# EnviroTron.net
KiCad netlist of a schematic drawn in EAGLE
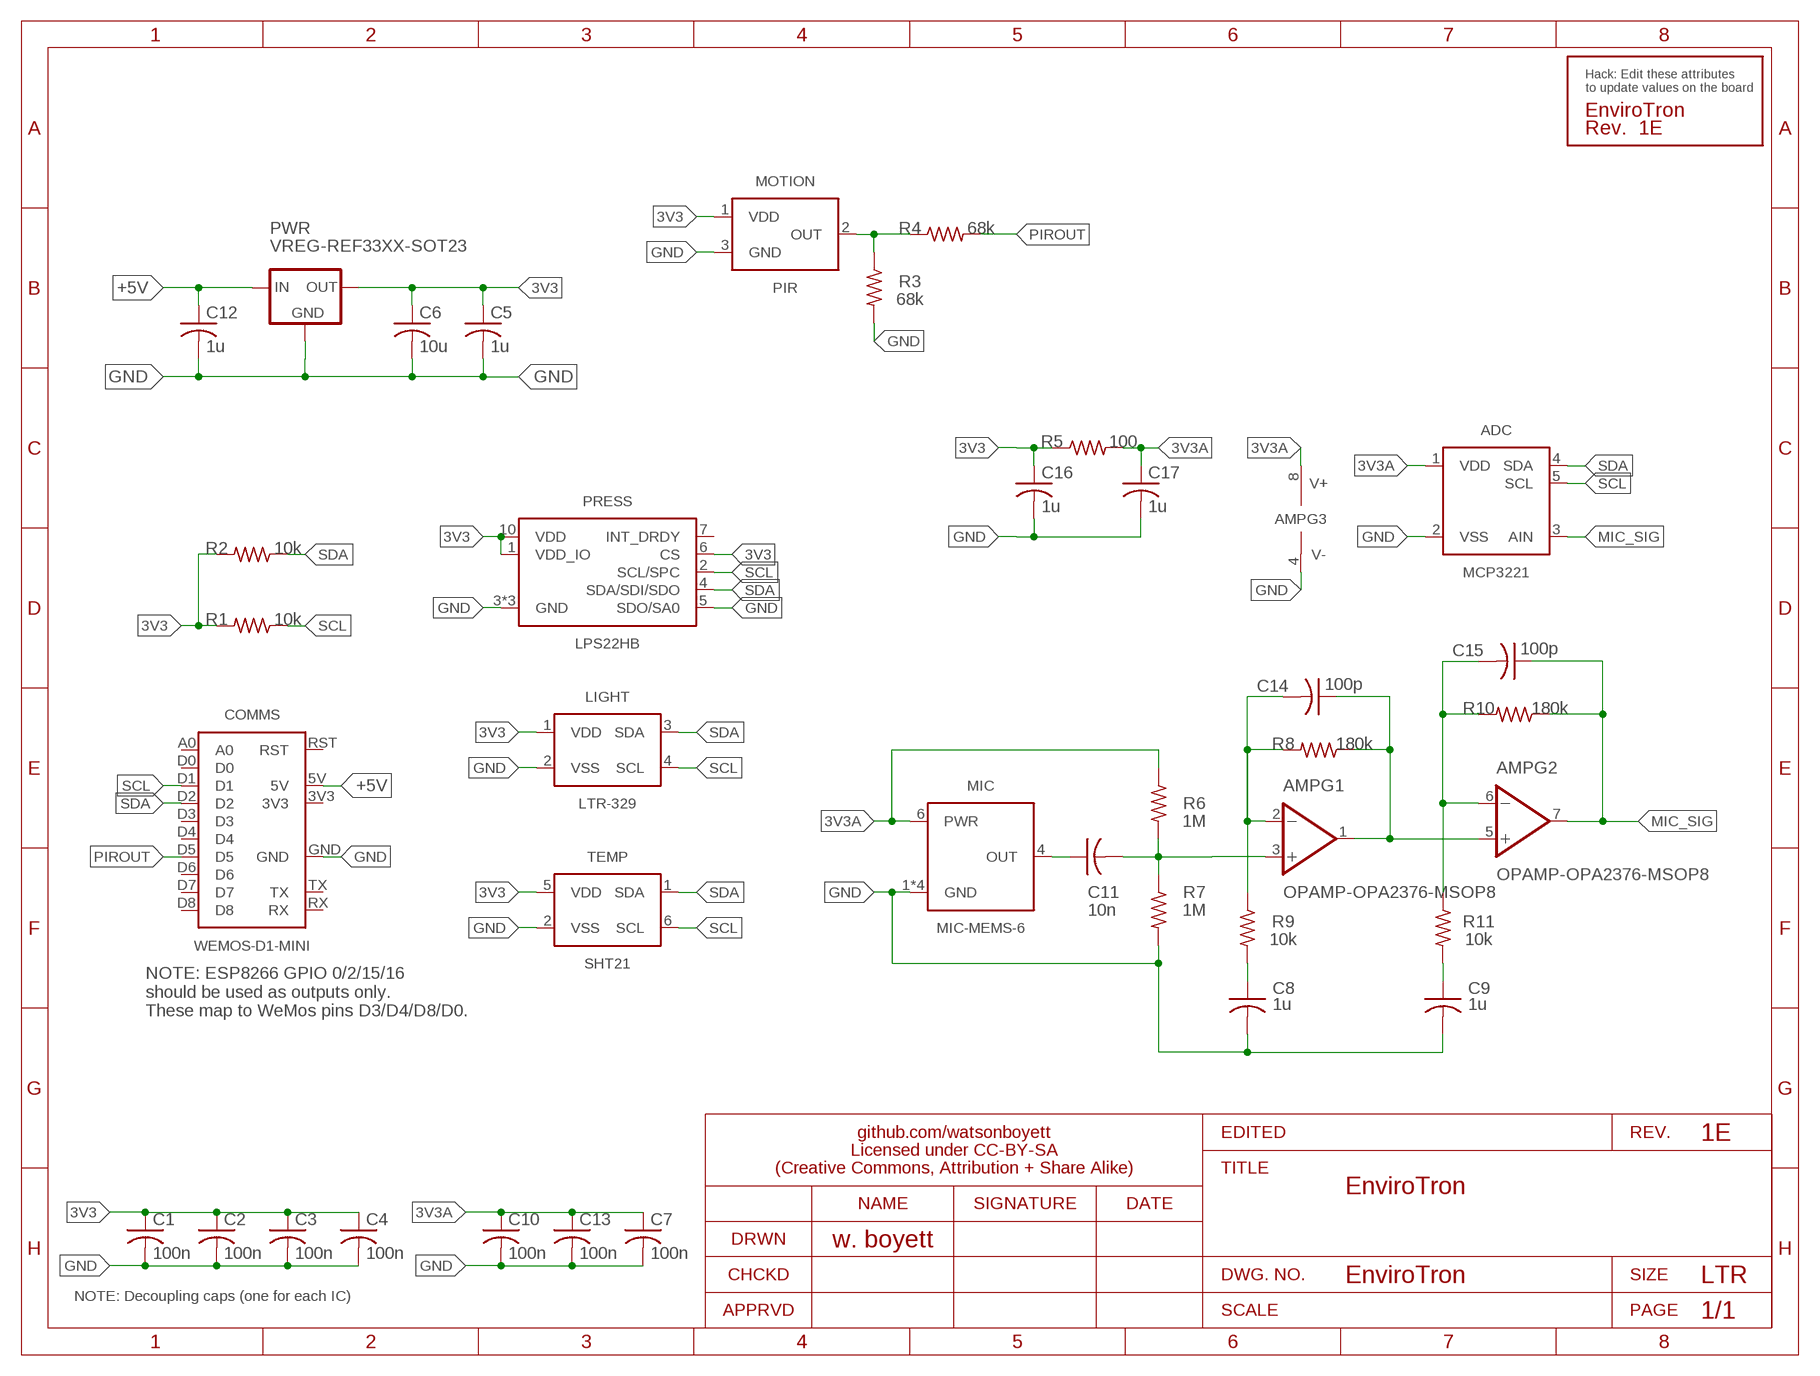
[diagram p0: schematic, sheet 1]

(export (version "E")
  (design (tool "Eeschema 10.0.6"))
  (components
    (comp (ref "ADC")
      (value "MCP3221")
      (footprint "eagle-import:SOT23-5")
      (fields (field (name "MFG") "Microchip Technology") (field (name "MPN") "MCP3221A5T-I/OT"))
      (libsource (lib "eagle-import") (part "MCP3221"))
    )
    (comp (ref "AMP")
      (value "OPAMP-OPA2376-MSOP8")
      (footprint "eagle-import:MSOP-8")
      (fields
        (field (name "MFG") "Texas Instruments")
        (field (name "MPN") "OPA2376AIDGKR")
        (field (name "SPICEPREFIX") "J")
      )
      (libsource (lib "eagle-import") (part "OPAMP-MSOP8-OPA2376"))
    )
    (comp (ref "C1")
      (value "100n")
      (footprint "eagle-import:C0603")
      (libsource (lib "eagle-import") (part "C-USC0603"))
    )
    (comp (ref "C2")
      (value "100n")
      (footprint "eagle-import:C0603")
      (libsource (lib "eagle-import") (part "C-USC0603"))
    )
    (comp (ref "C3")
      (value "100n")
      (footprint "eagle-import:C0603")
      (libsource (lib "eagle-import") (part "C-USC0603"))
    )
    (comp (ref "C4")
      (value "100n")
      (footprint "eagle-import:C0603")
      (libsource (lib "eagle-import") (part "C-USC0603"))
    )
    (comp (ref "C5")
      (value "1u")
      (footprint "eagle-import:C0603")
      (libsource (lib "eagle-import") (part "C-USC0603"))
    )
    (comp (ref "C6")
      (value "10u")
      (footprint "eagle-import:C0805")
      (libsource (lib "eagle-import") (part "C-USC0805"))
    )
    (comp (ref "C7")
      (value "100n")
      (footprint "eagle-import:C0603")
      (libsource (lib "eagle-import") (part "C-USC0603"))
    )
    (comp (ref "C8")
      (value "1u")
      (footprint "eagle-import:C0603")
      (libsource (lib "eagle-import") (part "C-USC0603"))
    )
    (comp (ref "C9")
      (value "1u")
      (footprint "eagle-import:C0603")
      (libsource (lib "eagle-import") (part "C-USC0603"))
    )
    (comp (ref "C10")
      (value "100n")
      (footprint "eagle-import:C0603")
      (libsource (lib "eagle-import") (part "C-USC0603"))
    )
    (comp (ref "C11")
      (value "10n")
      (footprint "eagle-import:C0603")
      (libsource (lib "eagle-import") (part "C-USC0603"))
    )
    (comp (ref "C12")
      (value "1u")
      (footprint "eagle-import:C0603")
      (libsource (lib "eagle-import") (part "C-USC0603"))
    )
    (comp (ref "C13")
      (value "100n")
      (footprint "eagle-import:C0603")
      (libsource (lib "eagle-import") (part "C-USC0603"))
    )
    (comp (ref "C14")
      (value "100p")
      (footprint "eagle-import:C0603")
      (libsource (lib "eagle-import") (part "C-USC0603"))
    )
    (comp (ref "C15")
      (value "100p")
      (footprint "eagle-import:C0603")
      (libsource (lib "eagle-import") (part "C-USC0603"))
    )
    (comp (ref "C16")
      (value "1u")
      (footprint "eagle-import:C0603")
      (libsource (lib "eagle-import") (part "C-USC0603"))
    )
    (comp (ref "C17")
      (value "1u")
      (footprint "eagle-import:C0603")
      (libsource (lib "eagle-import") (part "C-USC0603"))
    )
    (comp (ref "COMMS")
      (value "WEMOS-D1-MINI")
      (footprint "eagle-import:WEMOS-D1-MINI")
      (fields (field (name "SPICEPREFIX") "X"))
      (libsource (lib "eagle-import") (part "WEMOS-D1-MINI"))
    )
    (comp (ref "LIGHT")
      (value "LTR-329")
      (footprint "eagle-import:CHIPLED4")
      (fields (field (name "MFG") "Lite-On Inc.") (field (name "MPN") "LTR-329ALS-01"))
      (libsource (lib "eagle-import") (part "LTR-329"))
    )
    (comp (ref "MIC")
      (value "MIC-MEMS-6")
      (footprint "eagle-import:DFN-6")
      (libsource (lib "eagle-import") (part "MIC-MEMS-6"))
    )
    (comp (ref "MOTION")
      (value "PIR")
      (footprint "eagle-import:CAN3")
      (fields (field (name "MFG") "Panasonic Electric Works") (field (name "MPN") "EKMC1601112"))
      (libsource (lib "eagle-import") (part "PIR"))
    )
    (comp (ref "PRESS")
      (value "LPS22HB")
      (footprint "eagle-import:HLGA-10L")
      (fields (field (name "MFG") "STMicroelectronics") (field (name "MPN") "LPS22HBTR"))
      (libsource (lib "eagle-import") (part "LPS22HB"))
    )
    (comp (ref "PWR")
      (value "VREG-REF33XX-SOT23")
      (footprint "eagle-import:SOT23-3")
      (fields (field (name "MFG") "Texas Instruments") (field (name "MPN") "REF3033AIDBZR"))
      (libsource (lib "eagle-import") (part "VREG-REF33XX-SOT23"))
    )
    (comp (ref "R1")
      (value "10k")
      (footprint "eagle-import:R0603")
      (libsource (lib "eagle-import") (part "R-US_R0603"))
    )
    (comp (ref "R2")
      (value "10k")
      (footprint "eagle-import:R0603")
      (libsource (lib "eagle-import") (part "R-US_R0603"))
    )
    (comp (ref "R3")
      (value "68k")
      (footprint "eagle-import:R0603")
      (libsource (lib "eagle-import") (part "R-US_R0603"))
    )
    (comp (ref "R4")
      (value "68k")
      (footprint "eagle-import:R0603")
      (libsource (lib "eagle-import") (part "R-US_R0603"))
    )
    (comp (ref "R5")
      (value "100")
      (footprint "eagle-import:R0603")
      (libsource (lib "eagle-import") (part "R-US_R0603"))
    )
    (comp (ref "R6")
      (value "1M")
      (footprint "eagle-import:R0603")
      (libsource (lib "eagle-import") (part "R-US_R0603"))
    )
    (comp (ref "R7")
      (value "1M")
      (footprint "eagle-import:R0603")
      (libsource (lib "eagle-import") (part "R-US_R0603"))
    )
    (comp (ref "R8")
      (value "180k")
      (footprint "eagle-import:R0603")
      (libsource (lib "eagle-import") (part "R-US_R0603"))
    )
    (comp (ref "R9")
      (value "10k")
      (footprint "eagle-import:R0603")
      (libsource (lib "eagle-import") (part "R-US_R0603"))
    )
    (comp (ref "R10")
      (value "180k")
      (footprint "eagle-import:R0603")
      (libsource (lib "eagle-import") (part "R-US_R0603"))
    )
    (comp (ref "R11")
      (value "10k")
      (footprint "eagle-import:R0603")
      (libsource (lib "eagle-import") (part "R-US_R0603"))
    )
    (comp (ref "TEMP")
      (value "SHT21")
      (footprint "eagle-import:SHT2X-DFN6")
      (fields (field (name "MFG") "Sensirion AG"))
      (libsource (lib "eagle-import") (part "SHT21"))
    )
    (comp (ref "U$1")
      (value "SILK_QC")
      (footprint "eagle-import:SILK_QC")
      (fields (field (name "MPN") "DNP") (field (name "PRODUCT") "EnviroTron") (field (name "REV") "1E"))
      (libsource (lib "eagle-import") (part "SILK_QC"))
    )
  )
  (nets
    (net (code "1") (name "+5V") (class "Default")
      (node (ref "C12") (pin "1") (pinfunction "1_1") (pintype "passive"))
      (node (ref "COMMS") (pin "5V") (pinfunction "5V_5V") (pintype "bidirectional"))
      (node (ref "PWR") (pin "1") (pinfunction "IN_1") (pintype "input"))
    )
    (net (code "2") (name "3V3") (class "Default")
      (node (ref "C1") (pin "1") (pinfunction "1_1") (pintype "passive"))
      (node (ref "C16") (pin "1") (pinfunction "1_1") (pintype "passive"))
      (node (ref "C2") (pin "1") (pinfunction "1_1") (pintype "passive"))
      (node (ref "C3") (pin "1") (pinfunction "1_1") (pintype "passive"))
      (node (ref "C4") (pin "1") (pinfunction "1_1") (pintype "passive"))
      (node (ref "C5") (pin "1") (pinfunction "1_1") (pintype "passive"))
      (node (ref "C6") (pin "1") (pinfunction "1_1") (pintype "passive"))
      (node (ref "LIGHT") (pin "1") (pinfunction "VDD_1") (pintype "bidirectional"))
      (node (ref "MOTION") (pin "1") (pinfunction "VDD_1") (pintype "bidirectional"))
      (node (ref "PRESS") (pin "1") (pinfunction "VDD_IO_1") (pintype "bidirectional"))
      (node (ref "PRESS") (pin "10") (pinfunction "VDD_10") (pintype "bidirectional"))
      (node (ref "PRESS") (pin "6") (pinfunction "CS_6") (pintype "bidirectional"))
      (node (ref "PWR") (pin "2") (pinfunction "OUT_2") (pintype "passive"))
      (node (ref "R1") (pin "2") (pinfunction "2_2") (pintype "passive"))
      (node (ref "R2") (pin "2") (pinfunction "2_2") (pintype "passive"))
      (node (ref "R5") (pin "1") (pinfunction "1_1") (pintype "passive"))
      (node (ref "TEMP") (pin "5") (pinfunction "VDD_5") (pintype "bidirectional"))
    )
    (net (code "3") (name "3V3A") (class "Default")
      (node (ref "ADC") (pin "1") (pinfunction "VDD_1") (pintype "bidirectional"))
      (node (ref "AMP") (pin "8") (pinfunction "V+_8") (pintype "power_in"))
      (node (ref "C10") (pin "1") (pinfunction "1_1") (pintype "passive"))
      (node (ref "C13") (pin "1") (pinfunction "1_1") (pintype "passive"))
      (node (ref "C17") (pin "1") (pinfunction "1_1") (pintype "passive"))
      (node (ref "C7") (pin "1") (pinfunction "1_1") (pintype "passive"))
      (node (ref "MIC") (pin "6") (pinfunction "PWR_6") (pintype "bidirectional"))
      (node (ref "R5") (pin "2") (pinfunction "2_2") (pintype "passive"))
      (node (ref "R6") (pin "1") (pinfunction "1_1") (pintype "passive"))
    )
    (net (code "4") (name "GND") (class "Default")
      (node (ref "ADC") (pin "2") (pinfunction "VSS_2") (pintype "bidirectional"))
      (node (ref "AMP") (pin "4") (pinfunction "V-_4") (pintype "power_in"))
      (node (ref "C1") (pin "2") (pinfunction "2_2") (pintype "passive"))
      (node (ref "C10") (pin "2") (pinfunction "2_2") (pintype "passive"))
      (node (ref "C12") (pin "2") (pinfunction "2_2") (pintype "passive"))
      (node (ref "C13") (pin "2") (pinfunction "2_2") (pintype "passive"))
      (node (ref "C16") (pin "2") (pinfunction "2_2") (pintype "passive"))
      (node (ref "C17") (pin "2") (pinfunction "2_2") (pintype "passive"))
      (node (ref "C2") (pin "2") (pinfunction "2_2") (pintype "passive"))
      (node (ref "C3") (pin "2") (pinfunction "2_2") (pintype "passive"))
      (node (ref "C4") (pin "2") (pinfunction "2_2") (pintype "passive"))
      (node (ref "C5") (pin "2") (pinfunction "2_2") (pintype "passive"))
      (node (ref "C6") (pin "2") (pinfunction "2_2") (pintype "passive"))
      (node (ref "C7") (pin "2") (pinfunction "2_2") (pintype "passive"))
      (node (ref "C8") (pin "2") (pinfunction "2_2") (pintype "passive"))
      (node (ref "C9") (pin "2") (pinfunction "2_2") (pintype "passive"))
      (node (ref "COMMS") (pin "GND") (pinfunction "GND_GND") (pintype "bidirectional"))
      (node (ref "LIGHT") (pin "2") (pinfunction "VSS_2") (pintype "bidirectional"))
      (node (ref "MIC") (pin "1") (pinfunction "GND_1") (pintype "bidirectional"))
      (node (ref "MIC") (pin "2") (pinfunction "GND_2") (pintype "bidirectional"))
      (node (ref "MIC") (pin "3") (pinfunction "GND_3") (pintype "bidirectional"))
      (node (ref "MIC") (pin "5") (pinfunction "GND_5") (pintype "bidirectional"))
      (node (ref "MOTION") (pin "3") (pinfunction "GND_3") (pintype "bidirectional"))
      (node (ref "PRESS") (pin "3") (pinfunction "GND_3") (pintype "bidirectional"))
      (node (ref "PRESS") (pin "5") (pinfunction "SDO/SA0_5") (pintype "bidirectional"))
      (node (ref "PRESS") (pin "8") (pinfunction "GND_8") (pintype "bidirectional"))
      (node (ref "PRESS") (pin "9") (pinfunction "GND_9") (pintype "bidirectional"))
      (node (ref "PWR") (pin "3") (pinfunction "GND_3") (pintype "input"))
      (node (ref "R3") (pin "2") (pinfunction "2_2") (pintype "passive"))
      (node (ref "R7") (pin "2") (pinfunction "2_2") (pintype "passive"))
      (node (ref "TEMP") (pin "2") (pinfunction "VSS_2") (pintype "bidirectional"))
    )
    (net (code "5") (name "MIC_SIG") (class "Default")
      (node (ref "ADC") (pin "3") (pinfunction "AIN_3") (pintype "bidirectional"))
      (node (ref "AMP") (pin "7") (pinfunction "OUT_7") (pintype "output"))
      (node (ref "C15") (pin "1") (pinfunction "1_1") (pintype "passive"))
      (node (ref "R10") (pin "1") (pinfunction "1_1") (pintype "passive"))
    )
    (net (code "6") (name "Net-(AMPA-+IN)") (class "Default")
      (node (ref "AMP") (pin "3") (pinfunction "+IN_3") (pintype "input"))
      (node (ref "C11") (pin "2") (pinfunction "2_2") (pintype "passive"))
      (node (ref "R6") (pin "2") (pinfunction "2_2") (pintype "passive"))
      (node (ref "R7") (pin "1") (pinfunction "1_1") (pintype "passive"))
    )
    (net (code "7") (name "Net-(AMPA--IN)") (class "Default")
      (node (ref "AMP") (pin "2") (pinfunction "-IN_2") (pintype "input"))
      (node (ref "C14") (pin "2") (pinfunction "2_2") (pintype "passive"))
      (node (ref "R8") (pin "2") (pinfunction "2_2") (pintype "passive"))
      (node (ref "R9") (pin "1") (pinfunction "1_1") (pintype "passive"))
    )
    (net (code "8") (name "Net-(AMPA-OUT)") (class "Default")
      (node (ref "AMP") (pin "1") (pinfunction "OUT_1") (pintype "output"))
      (node (ref "AMP") (pin "5") (pinfunction "+IN_5") (pintype "input"))
      (node (ref "C14") (pin "1") (pinfunction "1_1") (pintype "passive"))
      (node (ref "R8") (pin "1") (pinfunction "1_1") (pintype "passive"))
    )
    (net (code "9") (name "Net-(AMPB--IN)") (class "Default")
      (node (ref "AMP") (pin "6") (pinfunction "-IN_6") (pintype "input"))
      (node (ref "C15") (pin "2") (pinfunction "2_2") (pintype "passive"))
      (node (ref "R10") (pin "2") (pinfunction "2_2") (pintype "passive"))
      (node (ref "R11") (pin "1") (pinfunction "1_1") (pintype "passive"))
    )
    (net (code "10") (name "Net-(C8-Pad1)") (class "Default")
      (node (ref "C8") (pin "1") (pinfunction "1_1") (pintype "passive"))
      (node (ref "R9") (pin "2") (pinfunction "2_2") (pintype "passive"))
    )
    (net (code "11") (name "Net-(C9-Pad1)") (class "Default")
      (node (ref "C9") (pin "1") (pinfunction "1_1") (pintype "passive"))
      (node (ref "R11") (pin "2") (pinfunction "2_2") (pintype "passive"))
    )
    (net (code "12") (name "Net-(MIC-OUT)") (class "Default")
      (node (ref "C11") (pin "1") (pinfunction "1_1") (pintype "passive"))
      (node (ref "MIC") (pin "4") (pinfunction "OUT_4") (pintype "bidirectional"))
    )
    (net (code "13") (name "Net-(MOTION-OUT)") (class "Default")
      (node (ref "MOTION") (pin "2") (pinfunction "OUT_2") (pintype "bidirectional"))
      (node (ref "R3") (pin "1") (pinfunction "1_1") (pintype "passive"))
      (node (ref "R4") (pin "1") (pinfunction "1_1") (pintype "passive"))
    )
    (net (code "14") (name "PIROUT") (class "Default")
      (node (ref "COMMS") (pin "D5") (pinfunction "D5_D5") (pintype "bidirectional"))
      (node (ref "R4") (pin "2") (pinfunction "2_2") (pintype "passive"))
    )
    (net (code "15") (name "SCL") (class "Default")
      (node (ref "ADC") (pin "5") (pinfunction "SCL_5") (pintype "bidirectional"))
      (node (ref "COMMS") (pin "D1") (pinfunction "D1_D1") (pintype "bidirectional"))
      (node (ref "LIGHT") (pin "4") (pinfunction "SCL_4") (pintype "bidirectional"))
      (node (ref "PRESS") (pin "2") (pinfunction "SCL/SPC_2") (pintype "bidirectional"))
      (node (ref "R1") (pin "1") (pinfunction "1_1") (pintype "passive"))
      (node (ref "TEMP") (pin "6") (pinfunction "SCL_6") (pintype "bidirectional"))
    )
    (net (code "16") (name "SDA") (class "Default")
      (node (ref "ADC") (pin "4") (pinfunction "SDA_4") (pintype "bidirectional"))
      (node (ref "COMMS") (pin "D2") (pinfunction "D2_D2") (pintype "bidirectional"))
      (node (ref "LIGHT") (pin "3") (pinfunction "SDA_3") (pintype "bidirectional"))
      (node (ref "PRESS") (pin "4") (pinfunction "SDA/SDI/SDO_4") (pintype "bidirectional"))
      (node (ref "R2") (pin "1") (pinfunction "1_1") (pintype "passive"))
      (node (ref "TEMP") (pin "1") (pinfunction "SDA_1") (pintype "bidirectional"))
    )
    (net (code "17") (name "unconnected-(COMMS-Pad3V3)") (class "Default")
      (node (ref "COMMS") (pin "3V3") (pinfunction "3V3_3V3") (pintype "bidirectional"))
    )
    (net (code "18") (name "unconnected-(COMMS-PadA0)") (class "Default")
      (node (ref "COMMS") (pin "A0") (pinfunction "A0_A0") (pintype "bidirectional"))
    )
    (net (code "19") (name "unconnected-(COMMS-PadD0)") (class "Default")
      (node (ref "COMMS") (pin "D0") (pinfunction "D0_D0") (pintype "bidirectional"))
    )
    (net (code "20") (name "unconnected-(COMMS-PadD3)") (class "Default")
      (node (ref "COMMS") (pin "D3") (pinfunction "D3_D3") (pintype "bidirectional"))
    )
    (net (code "21") (name "unconnected-(COMMS-PadD4)") (class "Default")
      (node (ref "COMMS") (pin "D4") (pinfunction "D4_D4") (pintype "bidirectional"))
    )
    (net (code "22") (name "unconnected-(COMMS-PadD6)") (class "Default")
      (node (ref "COMMS") (pin "D6") (pinfunction "D6_D6") (pintype "bidirectional"))
    )
    (net (code "23") (name "unconnected-(COMMS-PadD7)") (class "Default")
      (node (ref "COMMS") (pin "D7") (pinfunction "D7_D7") (pintype "bidirectional"))
    )
    (net (code "24") (name "unconnected-(COMMS-PadD8)") (class "Default")
      (node (ref "COMMS") (pin "D8") (pinfunction "D8_D8") (pintype "bidirectional"))
    )
    (net (code "25") (name "unconnected-(COMMS-PadRST)") (class "Default")
      (node (ref "COMMS") (pin "RST") (pinfunction "RST_RST") (pintype "bidirectional"))
    )
    (net (code "26") (name "unconnected-(COMMS-PadRX)") (class "Default")
      (node (ref "COMMS") (pin "RX") (pinfunction "RX_RX") (pintype "bidirectional"))
    )
    (net (code "27") (name "unconnected-(COMMS-PadTX)") (class "Default")
      (node (ref "COMMS") (pin "TX") (pinfunction "TX_TX") (pintype "bidirectional"))
    )
    (net (code "28") (name "unconnected-(PRESS-INT_DRDY-Pad7)") (class "Default")
      (node (ref "PRESS") (pin "7") (pinfunction "INT_DRDY_7") (pintype "bidirectional"))
    )
  )
)
